# POWER_CN_BETTER.net
KiCad netlist of a schematic drawn in Altium Designer
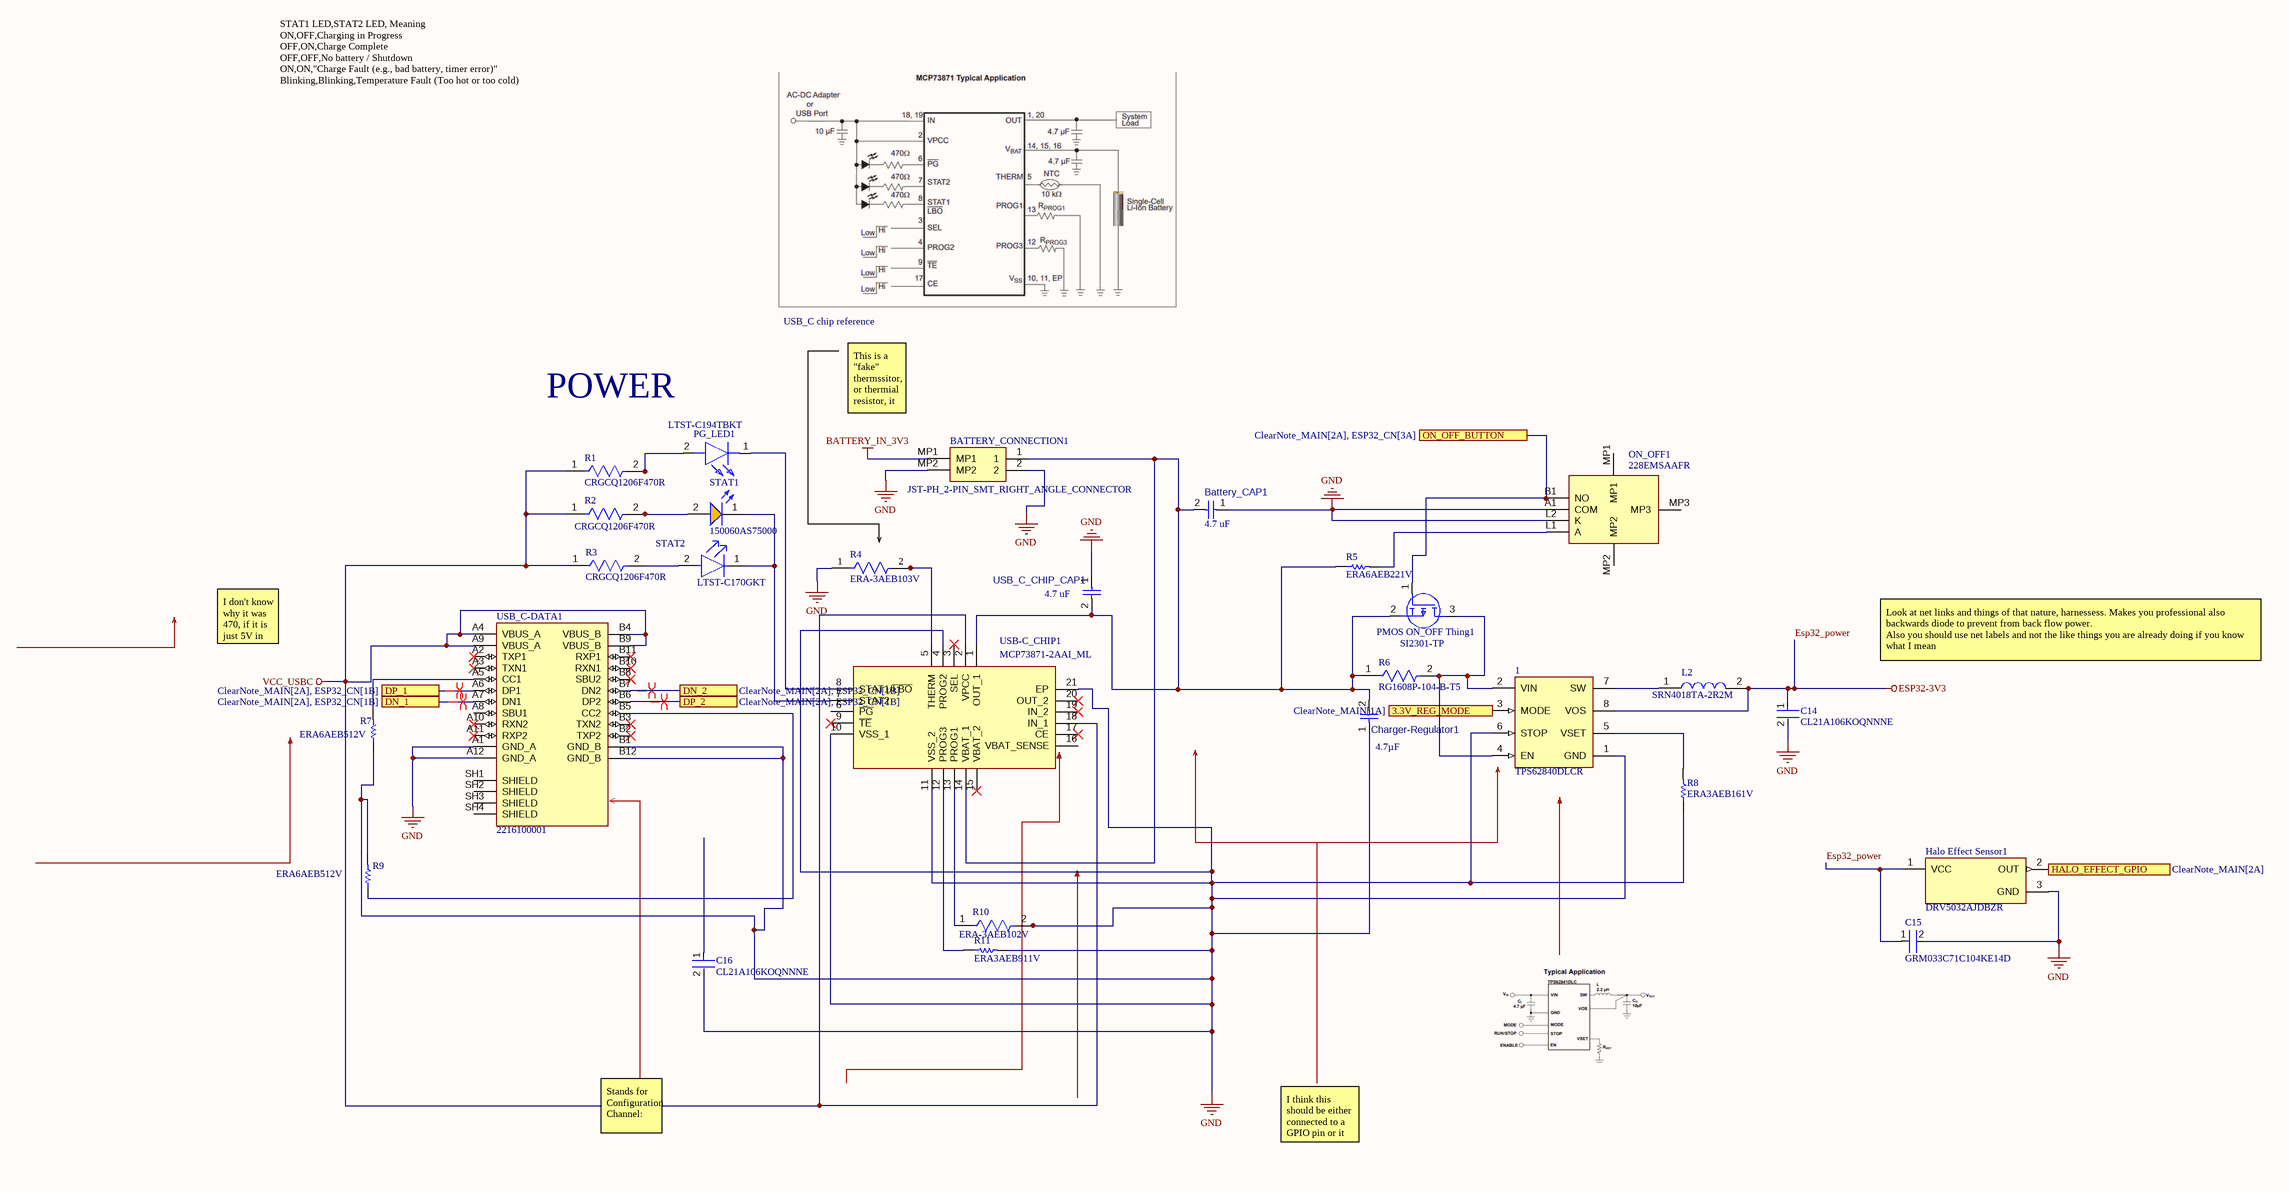
[diagram p0: POWER_CN_BETTER.SchDoc]

(export (version "E")
  (design (tool "Eeschema 10.0.6"))
  (components
    (comp (ref "1")
      (value "TPS62840DLCR")
      (footprint "FP-DLC0008B-MFG")
      (description "ULTRA LOW IQ BUCK CONVERTER")
      (fields
        (field (name "OCTOPART") "https://octopart.com/tps62840dlcr-texas+instruments-103121111")
        (field (name "MANUFACTURER") "Texas Instruments")
      )
      (libsource (lib "Altium Content Vault") (part "09bc3a9b1d58a1376198d6b923e8c7c"))
    )
    (comp (ref "Battery_CAP1")
      (value "4.7 uF")
      (footprint "CAPC0402(1005)60_L")
      (description "Chip Capacitor, 10µF +/-40%, 6.3V, 0402, Thickness 0.6 mm")
      (fields (field (name "TOLERANCE") "10%") (field (name "Comment") "Capacitor 10µF +/-40% 6.3V 0402"))
      (libsource (lib "CAN Board") (part "CAP-NP-2"))
    )
    (comp (ref "BATTERY_CONNECTION1")
      (value "JST-PH_2-PIN_SMT_RIGHT_ANGLE_CONNECTOR")
      (footprint "SamacSys:JSTPH2PINSMTRIGHTANGLECONNECTOR")
      (description "Connector")
      (fields (field (name "MANUFACTURER_PART_NUMBER") "JST-PH 2-PIN SMT RIGHT ANGLE CONNECTOR"))
      (libsource (lib "*") (part "JST-PH_2-PIN_SMT_RIGHT_ANGLE_CONNECTOR"))
    )
    (comp (ref "C14")
      (value "CL21A106KOQNNNE")
      (footprint "FP-CL21-IPC_B")
      (description "CL21 Series 0805 10uF 16V ±10% Tolerance X5R Multilayer Ceramic Chip Capacitor")
      (fields (field (name "VOLTAGE") "16V") (field (name "TOLERANCE") "10%"))
      (libsource (lib "Altium Content Vault") (part "b4654b650e69147ec39a6b967a45e02"))
    )
    (comp (ref "C15")
      (value "GRM033C71C104KE14D")
      (footprint "FP-GRM033-0_03-MFG")
      (description "Chip Multilayer Ceramic Capacitors for General Purpose, 0201, 0.10uF, X7S, 22%, 10%, 16V")
      (fields (field (name "TOLERANCE") "10%"))
      (libsource (lib "Altium Content Vault") (part "b4654b650e69147ec39a6b967a45e02"))
    )
    (comp (ref "C16")
      (value "CL21A106KOQNNNE")
      (footprint "FP-CL21-IPC_B")
      (description "CL21 Series 0805 10uF 16V ±10% Tolerance X5R Multilayer Ceramic Chip Capacitor")
      (fields (field (name "VOLTAGE") "16V") (field (name "TOLERANCE") "10%"))
      (libsource (lib "Altium Content Vault") (part "b4654b650e69147ec39a6b967a45e02"))
    )
    (comp (ref "Charger-Regulator1")
      (value "4.7µF")
      (footprint "CAPC0603(1608)100_L")
      (description "Chip Capacitor, 4.7µF +/-20%, 10V, 0603, Thickness 1 mm")
      (fields (field (name "TOLERANCE") "10%") (field (name "Comment") "Capacitor 4.7µF +/-20% 10V 0603"))
      (libsource (lib "CAN Board") (part "CAP-NP-2"))
    )
    (comp (ref "Halo Effect Sensor1")
      (value "DRV5032AJDBZR")
      (footprint "FP-DBZ0003A-MFG")
      (description "LP HALL 32AJDBZR/DNCR")
      (libsource (lib "Altium Content Vault") (part "4e2db082ab88a4546a189bae6fee1df"))
    )
    (comp (ref "L2")
      (value "SRN4018TA-2R2M")
      (footprint "SamacSys:SRN4018TA2R2M")
      (description "Inductor")
      (fields (field (name "MOUSER PART NUMBER") "652-SRN4018TA-2R2M"))
      (libsource (lib "*") (part "SRN4018TA-2R2M"))
    )
    (comp (ref "ON_OFF1")
      (value "228EMSAAFR")
      (footprint "SamacSys:228EMSAAFR")
      (description "Switch")
      (fields (field (name "MOUSER PART NUMBER") "774-228EMSAAFR"))
      (libsource (lib "*") (part "228EMSAAFR"))
    )
    (comp (ref "PG_LED1")
      (value "LTST-C194TBKT")
      (footprint "SamacSys:LEDC1608X35N")
      (description "LED")
      (fields (field (name "MOUSER PART NUMBER") "859-LTST-C194TBKT"))
      (libsource (lib "*") (part "LTST-C194TBKT"))
    )
    (comp (ref "PMOS ON_OFF Thing1")
      (value "SI2301-TP")
      (footprint "SamacSys:SOT95P237X125-3N")
      (description "MOSFET (P-Channel)")
      (fields (field (name "MOUSER PART NUMBER") "833-SI2301-TP"))
      (libsource (lib "*") (part "SI2301-TP"))
    )
    (comp (ref "R1")
      (value "CRGCQ1206F470R")
      (footprint "FP-CRGCQ1206-IPC_C")
      (description "CRGCQ 1206 470R 1%")
      (fields
        (field (name "OCTOPART") "https://octopart.com/crgcq1206f470r-te+connectivity-91018284")
        (field (name "TOLERANCE") "0.01")
      )
      (libsource (lib "Altium Content Vault") (part "1029c3af85768c4190bb7ad29bc67b5"))
    )
    (comp (ref "R2")
      (value "CRGCQ1206F470R")
      (footprint "FP-CRGCQ1206-IPC_C")
      (description "CRGCQ 1206 470R 1%")
      (fields
        (field (name "OCTOPART") "https://octopart.com/crgcq1206f470r-te+connectivity-91018284")
        (field (name "TOLERANCE") "0.01")
      )
      (libsource (lib "Altium Content Vault") (part "1029c3af85768c4190bb7ad29bc67b5"))
    )
    (comp (ref "R3")
      (value "CRGCQ1206F470R")
      (footprint "FP-CRGCQ1206-IPC_C")
      (description "CRGCQ 1206 470R 1%")
      (fields
        (field (name "OCTOPART") "https://octopart.com/crgcq1206f470r-te+connectivity-91018284")
        (field (name "TOLERANCE") "0.01")
      )
      (libsource (lib "Altium Content Vault") (part "1029c3af85768c4190bb7ad29bc67b5"))
    )
    (comp (ref "R4")
      (value "ERA-3AEB103V")
      (footprint "FP-ERA3A-IPC_C")
      (description "RES SMD 10K OHM 0.1% 1/10W 0603")
      (fields (field (name "TOLERANCE") "0.1%"))
      (libsource (lib "Altium Content Vault") (part "4e5f8b3dd332802e91518312df5df73"))
    )
    (comp (ref "R5")
      (value "ERA6AEB221V")
      (footprint "RESC2013X60X40NL20T25")
      (fields (field (name "MANUFACTURER") "Panasonic"))
      (libsource (lib "Altium Content Vault") (part "RES"))
    )
    (comp (ref "R6")
      (value "RG1608P-104-B-T5")
      (footprint "FP-RG1608-IPC_A")
      (description "Automotive Metal Thin Film Chip Resistor, 0603, 100kΩ, 0.1%, 25ppm/°C, 0.1W, 100V")
      (fields (field (name "TOLERANCE") "0.1%"))
      (libsource (lib "Altium Content Vault") (part "1029c3af85768c4190bb7ad29bc67b5"))
    )
    (comp (ref "R7")
      (value "ERA6AEB512V")
      (footprint "RESC2013X60X40LL20T25")
      (fields (field (name "MANUFACTURER") "Panasonic"))
      (libsource (lib "Altium Content Vault") (part "RES"))
    )
    (comp (ref "R8")
      (value "ERA3AEB161V")
      (footprint "RESC1608X55X30ML20T20")
      (fields (field (name "MANUFACTURER") "Panasonic"))
      (libsource (lib "Altium Content Vault") (part "RES"))
    )
    (comp (ref "R9")
      (value "ERA6AEB512V")
      (footprint "RESC2013X60X40LL20T25")
      (fields (field (name "MANUFACTURER") "Panasonic"))
      (libsource (lib "Altium Content Vault") (part "RES"))
    )
    (comp (ref "R10")
      (value "ERA-3AEB102V")
      (footprint "FP-ERA3A-IPC_C")
      (description "RES SMD 1K OHM 0.1% 1/10W 0603")
      (fields (field (name "TOLERANCE") "0.1%"))
      (libsource (lib "Altium Content Vault") (part "1029c3af85768c4190bb7ad29bc67b5"))
    )
    (comp (ref "R11")
      (value "ERA3AEB911V")
      (footprint "RESC1608X55X30NL20T20")
      (fields (field (name "MANUFACTURER") "Panasonic"))
      (libsource (lib "Altium Content Vault") (part "RES"))
    )
    (comp (ref "STAT1")
      (value "150060AS75000")
      (footprint "WL-SMCW_0603_150060xx75000")
      (description "WL-SMCW SMT Mono-Color Chip LED Waterclear")
      (libsource (lib "Altium Content Vault") (part "LED_Amber_2A-1K"))
    )
    (comp (ref "STAT2")
      (value "LTST-C170GKT")
      (footprint "FP-LTST-C170GKT-MFG")
      (description "LED GREEN CLEAR SMD")
      (fields (field (name "VOLTAGE") "5V"))
      (libsource (lib "Altium Content Vault") (part "8706943c75ba83719d021d2fdc84c58"))
    )
    (comp (ref "USB-C_CHIP1")
      (value "MCP73871-2AAI_ML")
      (footprint "SamacSys:QFN50P400X400X100-21N-D")
      (description "Integrated Circuit")
      (fields
        (field (name "MANUFACTURER_PART_NUMBER") "MCP73871-2AAI/ML")
        (field (name "MOUSER PART NUMBER") "579-MCP73871-2AAI/ML")
      )
      (libsource (lib "*") (part "MCP73871-2AAI_ML"))
    )
    (comp (ref "USB_C-DATA1")
      (value "2216100001")
      (footprint "MOLEX_2216100001")
      (description "USB-C (USB TYPE-C) Receptacle Connector 24 Position Surface Mount, Right Angle")
      (fields (field (name "MF") "Molex"))
      (libsource (lib "2216100001") (part "2216100001"))
    )
    (comp (ref "USB_C_CHIP_CAP1")
      (value "4.7 uF")
      (footprint "CAPC0402(1005)60_L")
      (description "Chip Capacitor, 10µF +/-40%, 6.3V, 0402, Thickness 0.6 mm")
      (fields (field (name "TOLERANCE") "10%") (field (name "Comment") "Capacitor 10µF +/-40% 6.3V 0402"))
      (libsource (lib "CAN Board") (part "CAP-NP-2"))
    )
  )
  (nets
    (net (code "1") (name "/3.3V_REG_MODE") (class "Default")
      (node (ref "1") (pin "3") (pinfunction "MODE_3") (pintype "input"))
    )
    (net (code "2") (name "/DN_1") (class "Default")
      (node (ref "USB_C-DATA1") (pin "A7") (pinfunction "DN1_A7") (pintype "bidirectional"))
    )
    (net (code "3") (name "/DN_2") (class "Default")
      (node (ref "USB_C-DATA1") (pin "B7") (pinfunction "DN2_B7") (pintype "bidirectional"))
    )
    (net (code "4") (name "/DP_1") (class "Default")
      (node (ref "USB_C-DATA1") (pin "A6") (pinfunction "DP1_A6") (pintype "bidirectional"))
    )
    (net (code "5") (name "/DP_2") (class "Default")
      (node (ref "USB_C-DATA1") (pin "B6") (pinfunction "DP2_B6") (pintype "bidirectional"))
    )
    (net (code "6") (name "/HALO_EFFECT_GPIO") (class "Default")
      (node (ref "Halo Effect Sensor1") (pin "2") (pinfunction "OUT_2") (pintype "output"))
    )
    (net (code "7") (name "/ON_OFF_BUTTON") (class "Default")
      (node (ref "ON_OFF1") (pin "B1") (pinfunction "NO_B1") (pintype "passive"))
      (node (ref "PMOS ON_OFF Thing1") (pin "1") (pinfunction "G_1") (pintype "passive"))
    )
    (net (code "8") (name "BATTERY_IN_3V3") (class "Default")
      (node (ref "BATTERY_CONNECTION1") (pin "MP1") (pinfunction "MP1_MP1") (pintype "passive"))
    )
    (net (code "9") (name "ESP32-3V3") (class "Default")
      (node (ref "1") (pin "8") (pinfunction "VOS_8") (pintype "passive"))
      (node (ref "C14") (pin "1") (pinfunction "1_1") (pintype "passive"))
      (node (ref "C15") (pin "1") (pinfunction "1_1") (pintype "passive"))
      (node (ref "Halo Effect Sensor1") (pin "1") (pinfunction "VCC_1") (pintype "power_in"))
      (node (ref "L2") (pin "2") (pinfunction "2_2") (pintype "passive"))
    )
    (net (code "10") (name "GND") (class "Default")
      (node (ref "1") (pin "1") (pinfunction "GND_1") (pintype "power_in"))
      (node (ref "1") (pin "6") (pinfunction "STOP_6") (pintype "input"))
      (node (ref "BATTERY_CONNECTION1") (pin "2") (pinfunction "2_2") (pintype "passive"))
      (node (ref "BATTERY_CONNECTION1") (pin "MP2") (pinfunction "MP2_MP2") (pintype "passive"))
      (node (ref "Battery_CAP1") (pin "1") (pinfunction "1_1") (pintype "passive"))
      (node (ref "C14") (pin "2") (pinfunction "2_2") (pintype "passive"))
      (node (ref "C15") (pin "2") (pinfunction "2_2") (pintype "passive"))
      (node (ref "C16") (pin "2") (pinfunction "2_2") (pintype "passive"))
      (node (ref "Charger-Regulator1") (pin "1") (pinfunction "1_1") (pintype "passive"))
      (node (ref "Halo Effect Sensor1") (pin "3") (pinfunction "GND_3") (pintype "power_in"))
      (node (ref "ON_OFF1") (pin "A1") (pinfunction "COM_A1") (pintype "passive"))
      (node (ref "ON_OFF1") (pin "L2") (pinfunction "K_L2") (pintype "passive"))
      (node (ref "R10") (pin "2") (pinfunction "2_2") (pintype "passive"))
      (node (ref "R11") (pin "2") (pinfunction "2_2") (pintype "passive"))
      (node (ref "R4") (pin "1") (pinfunction "1_1") (pintype "passive"))
      (node (ref "R7") (pin "1") (pinfunction "1_1") (pintype "passive"))
      (node (ref "R8") (pin "1") (pinfunction "1_1") (pintype "passive"))
      (node (ref "R9") (pin "2") (pinfunction "2_2") (pintype "passive"))
      (node (ref "USB-C_CHIP1") (pin "10") (pinfunction "VSS_1_10") (pintype "passive"))
      (node (ref "USB-C_CHIP1") (pin "11") (pinfunction "VSS_2_11") (pintype "passive"))
      (node (ref "USB-C_CHIP1") (pin "21") (pinfunction "EP_21") (pintype "passive"))
      (node (ref "USB-C_CHIP1") (pin "4") (pinfunction "PROG2_4") (pintype "passive"))
      (node (ref "USB_C-DATA1") (pin "A1") (pinfunction "GND_A_A1") (pintype "power_in"))
      (node (ref "USB_C-DATA1") (pin "A12") (pinfunction "GND_A_A12") (pintype "power_in"))
      (node (ref "USB_C-DATA1") (pin "B1") (pinfunction "GND_B_B1") (pintype "power_in"))
      (node (ref "USB_C-DATA1") (pin "B12") (pinfunction "GND_B_B12") (pintype "power_in"))
      (node (ref "USB_C_CHIP_CAP1") (pin "1") (pinfunction "1_1") (pintype "passive"))
    )
    (net (code "11") (name "Net-(1-EN)") (class "Default")
      (node (ref "1") (pin "2") (pinfunction "VIN_2") (pintype "power_in"))
      (node (ref "1") (pin "4") (pinfunction "EN_4") (pintype "input"))
      (node (ref "PMOS ON_OFF Thing1") (pin "3") (pinfunction "D_3") (pintype "passive"))
      (node (ref "R6") (pin "2") (pinfunction "2_2") (pintype "passive"))
    )
    (net (code "12") (name "Net-(1-SW)") (class "Default")
      (node (ref "1") (pin "7") (pinfunction "SW_7") (pintype "passive"))
      (node (ref "L2") (pin "1") (pinfunction "1_1") (pintype "passive"))
    )
    (net (code "13") (name "Net-(1-VSET)") (class "Default")
      (node (ref "1") (pin "5") (pinfunction "VSET_5") (pintype "passive"))
      (node (ref "R8") (pin "2") (pinfunction "2_2") (pintype "passive"))
    )
    (net (code "14") (name "Net-(ON_OFF1-A)") (class "Default")
      (node (ref "ON_OFF1") (pin "L1") (pinfunction "A_L1") (pintype "passive"))
      (node (ref "R5") (pin "2") (pinfunction "2_2") (pintype "passive"))
    )
    (net (code "15") (name "Net-(PG_LED1-A)") (class "Default")
      (node (ref "PG_LED1") (pin "2") (pinfunction "A_2") (pintype "passive"))
      (node (ref "R1") (pin "2") (pinfunction "2_2") (pintype "passive"))
    )
    (net (code "16") (name "Net-(PG_LED1-K)") (class "Default")
      (node (ref "PG_LED1") (pin "1") (pinfunction "K_1") (pintype "passive"))
      (node (ref "USB-C_CHIP1") (pin "8") (pinfunction "STAT1/~{LBO}_8") (pintype "passive"))
    )
    (net (code "17") (name "Net-(PMOS ON_OFF Thing1-S)") (class "Default")
      (node (ref "BATTERY_CONNECTION1") (pin "1") (pinfunction "1_1") (pintype "passive"))
      (node (ref "Battery_CAP1") (pin "2") (pinfunction "2_2") (pintype "passive"))
      (node (ref "Charger-Regulator1") (pin "2") (pinfunction "2_2") (pintype "passive"))
      (node (ref "PMOS ON_OFF Thing1") (pin "2") (pinfunction "S_2") (pintype "passive"))
      (node (ref "R5") (pin "1") (pinfunction "1_1") (pintype "passive"))
      (node (ref "R6") (pin "1") (pinfunction "1_1") (pintype "passive"))
      (node (ref "USB-C_CHIP1") (pin "1") (pinfunction "OUT_1_1") (pintype "passive"))
      (node (ref "USB-C_CHIP1") (pin "14") (pinfunction "VBAT_1_14") (pintype "passive"))
      (node (ref "USB_C_CHIP_CAP1") (pin "2") (pinfunction "2_2") (pintype "passive"))
    )
    (net (code "18") (name "Net-(STAT1-A)") (class "Default")
      (node (ref "R2") (pin "2") (pinfunction "2_2") (pintype "passive"))
      (node (ref "STAT1") (pin "2") (pinfunction "A_2") (pintype "passive"))
    )
    (net (code "19") (name "Net-(STAT1-K)") (class "Default")
      (node (ref "STAT1") (pin "1") (pinfunction "K_1") (pintype "passive"))
      (node (ref "STAT2") (pin "1") (pinfunction "C_1") (pintype "passive"))
      (node (ref "USB-C_CHIP1") (pin "7") (pinfunction "STAT2_7") (pintype "passive"))
    )
    (net (code "20") (name "Net-(STAT2-A)") (class "Default")
      (node (ref "R3") (pin "2") (pinfunction "2_2") (pintype "passive"))
      (node (ref "STAT2") (pin "2") (pinfunction "A_2") (pintype "passive"))
    )
    (net (code "21") (name "Net-(USB-C_CHIP1-PROG1)") (class "Default")
      (node (ref "R10") (pin "1") (pinfunction "1_1") (pintype "passive"))
      (node (ref "USB-C_CHIP1") (pin "13") (pinfunction "PROG1_13") (pintype "passive"))
    )
    (net (code "22") (name "Net-(USB-C_CHIP1-PROG3)") (class "Default")
      (node (ref "R11") (pin "1") (pinfunction "1_1") (pintype "passive"))
      (node (ref "USB-C_CHIP1") (pin "12") (pinfunction "PROG3_12") (pintype "passive"))
    )
    (net (code "23") (name "Net-(USB-C_CHIP1-THERM)") (class "Default")
      (node (ref "R4") (pin "2") (pinfunction "2_2") (pintype "passive"))
      (node (ref "USB-C_CHIP1") (pin "5") (pinfunction "THERM_5") (pintype "passive"))
    )
    (net (code "24") (name "Net-(USB_C-DATA1-CC1)") (class "Default")
      (node (ref "R7") (pin "2") (pinfunction "2_2") (pintype "passive"))
      (node (ref "USB_C-DATA1") (pin "A5") (pinfunction "CC1_A5") (pintype "bidirectional"))
    )
    (net (code "25") (name "Net-(USB_C-DATA1-CC2)") (class "Default")
      (node (ref "R9") (pin "1") (pinfunction "1_1") (pintype "passive"))
      (node (ref "USB_C-DATA1") (pin "B5") (pinfunction "CC2_B5") (pintype "bidirectional"))
    )
    (net (code "26") (name "VCC_USBC") (class "Default")
      (node (ref "R1") (pin "1") (pinfunction "1_1") (pintype "passive"))
      (node (ref "R2") (pin "1") (pinfunction "1_1") (pintype "passive"))
      (node (ref "R3") (pin "1") (pinfunction "1_1") (pintype "passive"))
      (node (ref "USB-C_CHIP1") (pin "18") (pinfunction "IN_1_18") (pintype "passive"))
      (node (ref "USB-C_CHIP1") (pin "2") (pinfunction "VPCC_2") (pintype "passive"))
      (node (ref "USB_C-DATA1") (pin "A4") (pinfunction "VBUS_A_A4") (pintype "power_in"))
      (node (ref "USB_C-DATA1") (pin "A9") (pinfunction "VBUS_A_A9") (pintype "power_in"))
      (node (ref "USB_C-DATA1") (pin "B4") (pinfunction "VBUS_B_B4") (pintype "power_in"))
      (node (ref "USB_C-DATA1") (pin "B9") (pinfunction "VBUS_B_B9") (pintype "power_in"))
    )
    (net (code "27") (name "unconnected-(C16-Pad1)") (class "Default")
      (node (ref "C16") (pin "1") (pinfunction "1_1") (pintype "passive"))
    )
    (net (code "28") (name "unconnected-(ON_OFF1-PadMP1)") (class "Default")
      (node (ref "ON_OFF1") (pin "MP1") (pinfunction "MP1_MP1") (pintype "passive"))
    )
    (net (code "29") (name "unconnected-(ON_OFF1-PadMP2)") (class "Default")
      (node (ref "ON_OFF1") (pin "MP2") (pinfunction "MP2_MP2") (pintype "passive"))
    )
    (net (code "30") (name "unconnected-(ON_OFF1-PadMP3)") (class "Default")
      (node (ref "ON_OFF1") (pin "MP3") (pinfunction "MP3_MP3") (pintype "passive"))
    )
    (net (code "31") (name "unconnected-(USB-C_CHIP1-CE-Pad17)") (class "Default")
      (node (ref "USB-C_CHIP1") (pin "17") (pinfunction "CE_17") (pintype "passive+no_connect"))
    )
    (net (code "32") (name "unconnected-(USB-C_CHIP1-IN_2-Pad19)") (class "Default")
      (node (ref "USB-C_CHIP1") (pin "19") (pinfunction "IN_2_19") (pintype "passive+no_connect"))
    )
    (net (code "33") (name "unconnected-(USB-C_CHIP1-OUT_2-Pad20)") (class "Default")
      (node (ref "USB-C_CHIP1") (pin "20") (pinfunction "OUT_2_20") (pintype "passive+no_connect"))
    )
    (net (code "34") (name "unconnected-(USB-C_CHIP1-SEL-Pad3)") (class "Default")
      (node (ref "USB-C_CHIP1") (pin "3") (pinfunction "SEL_3") (pintype "passive+no_connect"))
    )
    (net (code "35") (name "unconnected-(USB-C_CHIP1-VBAT_2-Pad15)") (class "Default")
      (node (ref "USB-C_CHIP1") (pin "15") (pinfunction "VBAT_2_15") (pintype "passive+no_connect"))
    )
    (net (code "36") (name "unconnected-(USB-C_CHIP1-VBAT_SENSE-Pad16)") (class "Default")
      (node (ref "USB-C_CHIP1") (pin "16") (pinfunction "VBAT_SENSE_16") (pintype "passive"))
    )
    (net (code "37") (name "unconnected-(USB-C_CHIP1-~{PG}-Pad6)") (class "Default")
      (node (ref "USB-C_CHIP1") (pin "6") (pinfunction "~{PG}_6") (pintype "passive"))
    )
    (net (code "38") (name "unconnected-(USB-C_CHIP1-~{TE}-Pad9)") (class "Default")
      (node (ref "USB-C_CHIP1") (pin "9") (pinfunction "~{TE}_9") (pintype "passive+no_connect"))
    )
    (net (code "39") (name "unconnected-(USB_C-DATA1-RXN1-PadB10)") (class "Default")
      (node (ref "USB_C-DATA1") (pin "B10") (pinfunction "RXN1_B10") (pintype "bidirectional+no_connect"))
    )
    (net (code "40") (name "unconnected-(USB_C-DATA1-RXN2-PadA10)") (class "Default")
      (node (ref "USB_C-DATA1") (pin "A10") (pinfunction "RXN2_A10") (pintype "bidirectional+no_connect"))
    )
    (net (code "41") (name "unconnected-(USB_C-DATA1-RXP1-PadB11)") (class "Default")
      (node (ref "USB_C-DATA1") (pin "B11") (pinfunction "RXP1_B11") (pintype "bidirectional+no_connect"))
    )
    (net (code "42") (name "unconnected-(USB_C-DATA1-RXP2-PadA11)") (class "Default")
      (node (ref "USB_C-DATA1") (pin "A11") (pinfunction "RXP2_A11") (pintype "bidirectional+no_connect"))
    )
    (net (code "43") (name "unconnected-(USB_C-DATA1-SBU1-PadA8)") (class "Default")
      (node (ref "USB_C-DATA1") (pin "A8") (pinfunction "SBU1_A8") (pintype "bidirectional"))
    )
    (net (code "44") (name "unconnected-(USB_C-DATA1-SBU2-PadB8)") (class "Default")
      (node (ref "USB_C-DATA1") (pin "B8") (pinfunction "SBU2_B8") (pintype "bidirectional+no_connect"))
    )
    (net (code "45") (name "unconnected-(USB_C-DATA1-SHIELD-PadSH1)") (class "Default")
      (node (ref "USB_C-DATA1") (pin "SH1") (pinfunction "SHIELD_SH1") (pintype "passive"))
    )
    (net (code "46") (name "unconnected-(USB_C-DATA1-SHIELD-PadSH2)") (class "Default")
      (node (ref "USB_C-DATA1") (pin "SH2") (pinfunction "SHIELD_SH2") (pintype "passive"))
    )
    (net (code "47") (name "unconnected-(USB_C-DATA1-SHIELD-PadSH3)") (class "Default")
      (node (ref "USB_C-DATA1") (pin "SH3") (pinfunction "SHIELD_SH3") (pintype "passive"))
    )
    (net (code "48") (name "unconnected-(USB_C-DATA1-SHIELD-PadSH4)") (class "Default")
      (node (ref "USB_C-DATA1") (pin "SH4") (pinfunction "SHIELD_SH4") (pintype "passive"))
    )
    (net (code "49") (name "unconnected-(USB_C-DATA1-TXN1-PadA3)") (class "Default")
      (node (ref "USB_C-DATA1") (pin "A3") (pinfunction "TXN1_A3") (pintype "bidirectional+no_connect"))
    )
    (net (code "50") (name "unconnected-(USB_C-DATA1-TXN2-PadB3)") (class "Default")
      (node (ref "USB_C-DATA1") (pin "B3") (pinfunction "TXN2_B3") (pintype "bidirectional+no_connect"))
    )
    (net (code "51") (name "unconnected-(USB_C-DATA1-TXP1-PadA2)") (class "Default")
      (node (ref "USB_C-DATA1") (pin "A2") (pinfunction "TXP1_A2") (pintype "bidirectional+no_connect"))
    )
    (net (code "52") (name "unconnected-(USB_C-DATA1-TXP2-PadB2)") (class "Default")
      (node (ref "USB_C-DATA1") (pin "B2") (pinfunction "TXP2_B2") (pintype "bidirectional+no_connect"))
    )
  )
)
